# Camera_Shield_Power.net
KiCad netlist of a schematic drawn in Altium Designer
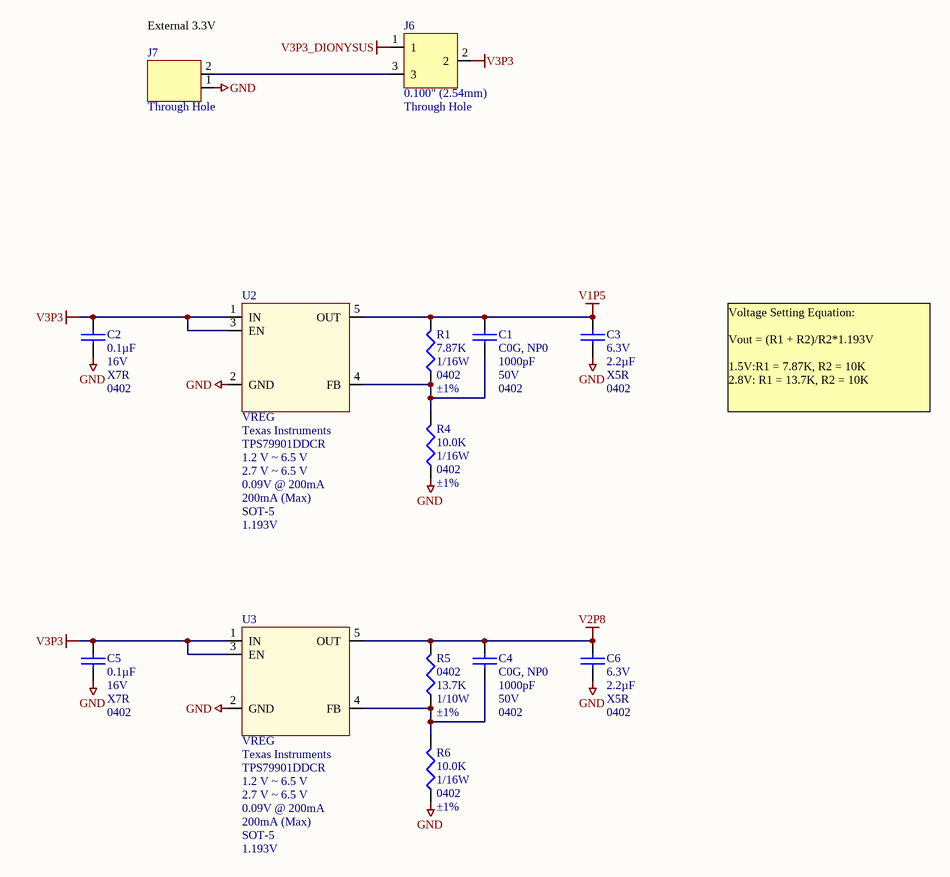
[diagram p0: Camera_Shield_Power.SchDoc]

(export (version "E")
  (design (tool "Eeschema 10.0.6"))
  (components
    (comp (ref "C1")
      (value "1000pF")
      (footprint "C_ERA-0402")
      (description "CAP CER 1000PF 50V C0G 0402")
      (fields
        (field (name "MANUFACTURER") "Murata Electronics North America")
        (field (name "MANUFACTURER PART NUMBER") "GRM1555C1H102JA01D")
        (field (name "TEMPERATURE COEFFICIENT") "C0G, NP0")
        (field (name "CAPACITANCE") "1000pF")
        (field (name "VOLTAGE - RATED") "50V")
        (field (name "PACKAGE / CASE") "0402")
      )
      (libsource (lib "Main Library") (part "C_0402_1000PF_50V"))
    )
    (comp (ref "C2")
      (value "0.1uF")
      (footprint "C_0402")
      (description "CAP CER .10UF 16V X7R 0402")
      (fields
        (field (name "MANUFACTURER") "TDK Corporation")
        (field (name "MANUFACTURER PART NUMBER") "C1005X7R1C104K")
        (field (name "CAPACITANCE") "0.1µF")
        (field (name "VOLTAGE - RATED") "16V")
        (field (name "TEMPERATURE COEFFICIENT") "X7R")
        (field (name "PACKAGE / CASE") "0402")
      )
      (libsource (lib "Main Library") (part "C_0402_0.1UF_16V"))
    )
    (comp (ref "C3")
      (value "2.2uF")
      (footprint "C_ERA-0402")
      (description "CAP CER 2.2UF 6.3V X5R 0402")
      (fields
        (field (name "MANUFACTURER") "TDK Corporation")
        (field (name "MANUFACTURER PART NUMBER") "C1005X5R0J225M")
        (field (name "VOLTAGE - RATED") "6.3V")
        (field (name "CAPACITANCE") "2.2µF")
        (field (name "TEMPERATURE COEFFICIENT") "X5R")
        (field (name "PACKAGE / CASE") "0402")
      )
      (libsource (lib "Main Library") (part "C_0402_2.2UF"))
    )
    (comp (ref "C4")
      (value "1000pF")
      (footprint "C_ERA-0402")
      (description "CAP CER 1000PF 50V C0G 0402")
      (fields
        (field (name "MANUFACTURER") "Murata Electronics North America")
        (field (name "MANUFACTURER PART NUMBER") "GRM1555C1H102JA01D")
        (field (name "TEMPERATURE COEFFICIENT") "C0G, NP0")
        (field (name "CAPACITANCE") "1000pF")
        (field (name "VOLTAGE - RATED") "50V")
        (field (name "PACKAGE / CASE") "0402")
      )
      (libsource (lib "Main Library") (part "C_0402_1000PF_50V"))
    )
    (comp (ref "C5")
      (value "0.1uF")
      (footprint "C_0402")
      (description "CAP CER .10UF 16V X7R 0402")
      (fields
        (field (name "MANUFACTURER") "TDK Corporation")
        (field (name "MANUFACTURER PART NUMBER") "C1005X7R1C104K")
        (field (name "CAPACITANCE") "0.1µF")
        (field (name "VOLTAGE - RATED") "16V")
        (field (name "TEMPERATURE COEFFICIENT") "X7R")
        (field (name "PACKAGE / CASE") "0402")
      )
      (libsource (lib "Main Library") (part "C_0402_0.1UF_16V"))
    )
    (comp (ref "C6")
      (value "2.2uF")
      (footprint "C_ERA-0402")
      (description "CAP CER 2.2UF 6.3V X5R 0402")
      (fields
        (field (name "MANUFACTURER") "TDK Corporation")
        (field (name "MANUFACTURER PART NUMBER") "C1005X5R0J225M")
        (field (name "VOLTAGE - RATED") "6.3V")
        (field (name "CAPACITANCE") "2.2µF")
        (field (name "TEMPERATURE COEFFICIENT") "X5R")
        (field (name "PACKAGE / CASE") "0402")
      )
      (libsource (lib "Main Library") (part "C_0402_2.2UF"))
    )
    (comp (ref "J6")
      (value "J_HDR1X3_JUMPER_SELECT")
      (footprint "HDR_1X3")
      (description "CONN HEADER .100\" 3POS TIN PCB")
      (fields
        (field (name "MANUFACTURER") "Samtec")
        (field (name "MANUFACTURER PART NUMBER") "TSW-103-07-T-S")
        (field (name "PITCH") "0.100\" (2.54mm)")
        (field (name "MOUNTING TYPE") "Through Hole")
      )
      (libsource (lib "Main LibraryX") (part "J_HDR1X3_JUMPER_SELECT"))
    )
    (comp (ref "J7")
      (value "J_HDR1X2_JUMPER")
      (footprint "HDR_1X2")
      (description "CONN HEADER .100\" 2POS TIN PCB")
      (fields
        (field (name "MANUFACTURER") "Samtec")
        (field (name "MANUFACTURER PART NUMBER") "TSW-102-07-T-S")
        (field (name "MOUNTING TYPE") "Through Hole")
      )
      (libsource (lib "Main LibraryX") (part "J_HDR1X2_JUMPER"))
    )
    (comp (ref "R1")
      (value "R_0402_7.87K")
      (footprint "R_0402")
      (description "RES 7.87K OHM 1/16W 1% 0402 SMD")
      (fields
        (field (name "MANUFACTURER") "Yageo")
        (field (name "MANUFACTURER PART NUMBER") "RC0402FR-077K87L")
        (field (name "RESISTANCE IN OHMS") "7.87K")
        (field (name "POWER (WATTS)") "1/16W")
        (field (name "CASE") "0402")
        (field (name "TOLERANCE") "±1%")
      )
      (libsource (lib "Main Library") (part "R_0402_7.87K"))
    )
    (comp (ref "R4")
      (value "R_0402_10.0K")
      (footprint "ERA-0402")
      (description "RES 10.0K OHM 1/16W 1% 0402 SMD")
      (fields
        (field (name "MANUFACTURER") "Stackpole Electronics Inc")
        (field (name "MANUFACTURER PART NUMBER") "RMCF0402FT10K0")
        (field (name "RESISTANCE IN OHMS") "10.0K")
        (field (name "POWER (WATTS)") "1/16W")
        (field (name "CASE") "0402")
        (field (name "TOLERANCE") "±1%")
      )
      (libsource (lib "Main Library") (part "R_0402_10.0K"))
    )
    (comp (ref "R5")
      (value "R_0402_13.7K")
      (footprint "ERA-0402")
      (description "RES 13.7K OHM 1/10W 1% 0402 SMD")
      (fields
        (field (name "MANUFACTURER") "Panasonic - ECG")
        (field (name "MANUFACTURER PART NUMBER") "ERJ-2RKF1372X")
        (field (name "PACKAGE / CASE") "0402")
        (field (name "RESISTANCE (OHMS)") "13.7K")
        (field (name "POWER (WATTS)") "1/10W")
        (field (name "TOLERANCE") "±1%")
      )
      (libsource (lib "Main Library") (part "R_0402_13.7K"))
    )
    (comp (ref "R6")
      (value "R_0402_10.0K")
      (footprint "ERA-0402")
      (description "RES 10.0K OHM 1/16W 1% 0402 SMD")
      (fields
        (field (name "MANUFACTURER") "Stackpole Electronics Inc")
        (field (name "MANUFACTURER PART NUMBER") "RMCF0402FT10K0")
        (field (name "RESISTANCE IN OHMS") "10.0K")
        (field (name "POWER (WATTS)") "1/16W")
        (field (name "CASE") "0402")
        (field (name "TOLERANCE") "±1%")
      )
      (libsource (lib "Main Library") (part "R_0402_10.0K"))
    )
    (comp (ref "U2")
      (value "VREG")
      (footprint "SOT95P280X90-5N")
      (description "IC REG LDO ADJ .2A TSOT-23-5")
      (fields
        (field (name "MANUFACTURER") "Texas Instruments")
        (field (name "MANUFACTURER PART NUMBER") "TPS79901DDCR")
        (field (name "VOLTAGE - OUTPUT") "1.2 V ~ 6.5 V")
        (field (name "VOLTAGE - INPUT") "2.7 V ~ 6.5 V")
        (field (name "VOLTAGE - DROPOUT (TYPICAL)") "0.09V @ 200mA")
        (field (name "CURRENT - OUTPUT") "200mA (Max)")
        (field (name "SUPPLIER DEVICE PACKAGE") "SOT-5")
        (field (name "VREF") "1.193V")
      )
      (libsource (lib "Main LibraryX") (part "U_TPS79901DDCR"))
    )
    (comp (ref "U3")
      (value "VREG")
      (footprint "SOT95P280X90-5N")
      (description "IC REG LDO ADJ .2A TSOT-23-5")
      (fields
        (field (name "MANUFACTURER") "Texas Instruments")
        (field (name "MANUFACTURER PART NUMBER") "TPS79901DDCR")
        (field (name "VOLTAGE - OUTPUT") "1.2 V ~ 6.5 V")
        (field (name "VOLTAGE - INPUT") "2.7 V ~ 6.5 V")
        (field (name "VOLTAGE - DROPOUT (TYPICAL)") "0.09V @ 200mA")
        (field (name "CURRENT - OUTPUT") "200mA (Max)")
        (field (name "SUPPLIER DEVICE PACKAGE") "SOT-5")
        (field (name "VREF") "1.193V")
      )
      (libsource (lib "Main LibraryX") (part "U_TPS79901DDCR"))
    )
  )
  (nets
    (net (code "1") (name "GND") (class "Default")
      (node (ref "C2") (pin "1") (pinfunction "1_1") (pintype "passive"))
      (node (ref "C3") (pin "1") (pinfunction "1_1") (pintype "passive"))
      (node (ref "C5") (pin "1") (pinfunction "1_1") (pintype "passive"))
      (node (ref "C6") (pin "1") (pinfunction "1_1") (pintype "passive"))
      (node (ref "J7") (pin "1") (pinfunction "1_1") (pintype "passive"))
      (node (ref "R4") (pin "2") (pinfunction "2_2") (pintype "passive"))
      (node (ref "R6") (pin "2") (pinfunction "2_2") (pintype "passive"))
      (node (ref "U2") (pin "2") (pinfunction "GND_2") (pintype "passive"))
      (node (ref "U3") (pin "2") (pinfunction "GND_2") (pintype "passive"))
    )
    (net (code "2") (name "Net-(J6-Pad3)") (class "Default")
      (node (ref "J6") (pin "3") (pinfunction "3_3") (pintype "passive"))
      (node (ref "J7") (pin "2") (pinfunction "2_2") (pintype "passive"))
    )
    (net (code "3") (name "Net-(U2-FB)") (class "Default")
      (node (ref "C1") (pin "1") (pinfunction "1_1") (pintype "passive"))
      (node (ref "R1") (pin "2") (pinfunction "2_2") (pintype "passive"))
      (node (ref "R4") (pin "1") (pinfunction "1_1") (pintype "passive"))
      (node (ref "U2") (pin "4") (pinfunction "FB_4") (pintype "passive"))
    )
    (net (code "4") (name "Net-(U3-FB)") (class "Default")
      (node (ref "C4") (pin "1") (pinfunction "1_1") (pintype "passive"))
      (node (ref "R5") (pin "2") (pinfunction "2_2") (pintype "passive"))
      (node (ref "R6") (pin "1") (pinfunction "1_1") (pintype "passive"))
      (node (ref "U3") (pin "4") (pinfunction "FB_4") (pintype "passive"))
    )
    (net (code "5") (name "V1P5") (class "Default")
      (node (ref "C1") (pin "2") (pinfunction "2_2") (pintype "passive"))
      (node (ref "C3") (pin "2") (pinfunction "2_2") (pintype "passive"))
      (node (ref "R1") (pin "1") (pinfunction "1_1") (pintype "passive"))
      (node (ref "U2") (pin "5") (pinfunction "OUT_5") (pintype "passive"))
    )
    (net (code "6") (name "V2P8") (class "Default")
      (node (ref "C4") (pin "2") (pinfunction "2_2") (pintype "passive"))
      (node (ref "C6") (pin "2") (pinfunction "2_2") (pintype "passive"))
      (node (ref "R5") (pin "1") (pinfunction "1_1") (pintype "passive"))
      (node (ref "U3") (pin "5") (pinfunction "OUT_5") (pintype "passive"))
    )
    (net (code "7") (name "V3P3") (class "Default")
      (node (ref "C2") (pin "2") (pinfunction "2_2") (pintype "passive"))
      (node (ref "C5") (pin "2") (pinfunction "2_2") (pintype "passive"))
      (node (ref "J6") (pin "2") (pinfunction "2_2") (pintype "passive"))
      (node (ref "U2") (pin "1") (pinfunction "IN_1") (pintype "passive"))
      (node (ref "U2") (pin "3") (pinfunction "EN_3") (pintype "passive"))
      (node (ref "U3") (pin "1") (pinfunction "IN_1") (pintype "passive"))
      (node (ref "U3") (pin "3") (pinfunction "EN_3") (pintype "passive"))
    )
    (net (code "8") (name "V3P3_DIONYSUS") (class "Default")
      (node (ref "J6") (pin "1") (pinfunction "1_1") (pintype "passive"))
    )
  )
)
